# ESC.net
KiCad netlist of a schematic drawn in Altium Designer
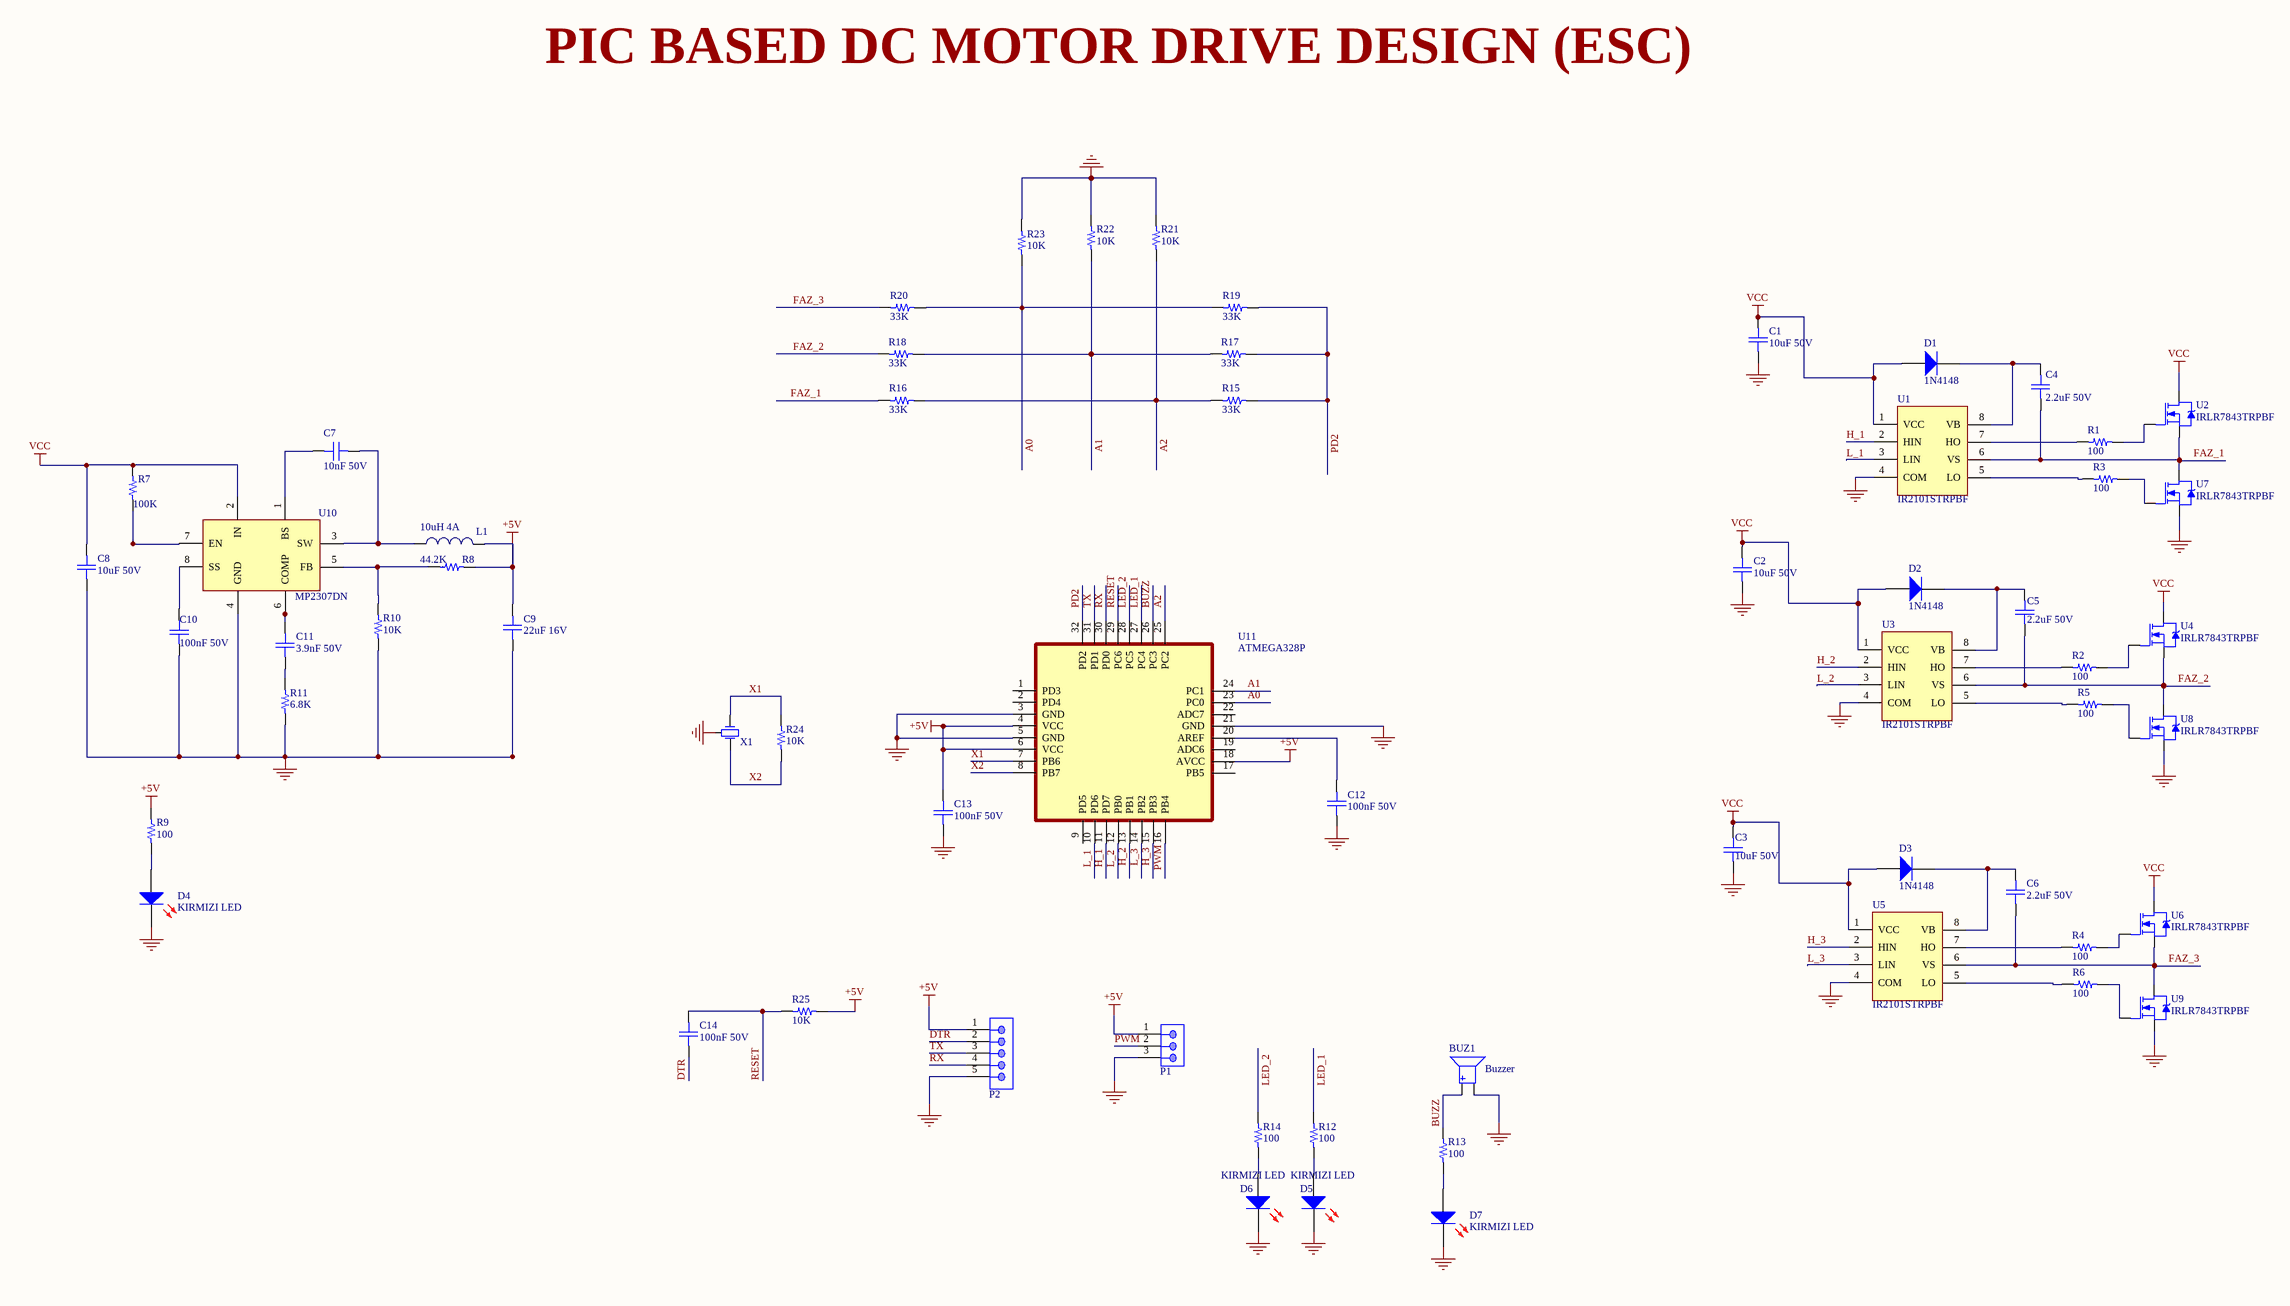
[diagram p0: ESC.SchDoc]

(export (version "E")
  (design (tool "Eeschema 10.0.6"))
  (components
    (comp (ref "BUZ1")
      (value "BUZZER MAGN 3.6V 7.5X7.5MM SMD")
      (footprint "BUZ: CMT-7525")
      (fields (field (name "DEGER") "Buzzer"))
      (libsource (lib "Suleyman Yukseldi") (part "Buzzer(CMT-7525-80-SMT-TR)"))
    )
    (comp (ref "C1")
      (value "CAP CER 10UF 50V X5R 1206")
      (footprint "CAP 1206/3216")
      (description "10µF ±10% 50V Ceramic Capacitor X5R 1206 (3216 Metric)")
      (fields (field (name "DEGER") "10uF 50V"))
      (libsource (lib "Suleyman Yukseldi") (part "10uF 50V 1206"))
    )
    (comp (ref "C2")
      (value "CAP CER 10UF 50V X5R 1206")
      (footprint "CAP 1206/3216")
      (description "10µF ±10% 50V Ceramic Capacitor X5R 1206 (3216 Metric)")
      (fields (field (name "DEGER") "10uF 50V"))
      (libsource (lib "Suleyman Yukseldi") (part "10uF 50V 1206"))
    )
    (comp (ref "C3")
      (value "CAP CER 10UF 50V X5R 1206")
      (footprint "CAP 1206/3216")
      (description "10µF ±10% 50V Ceramic Capacitor X5R 1206 (3216 Metric)")
      (fields (field (name "DEGER") "10uF 50V"))
      (libsource (lib "Suleyman Yukseldi") (part "10uF 50V 1206"))
    )
    (comp (ref "C4")
      (value "CAP CER 2.2UF 50V X5R 1206")
      (footprint "CAP 1206/3216")
      (description "2.2µF ±10% 50V Ceramic Capacitor X5R 1206 (3216 Metric)")
      (fields (field (name "DEGER") "2.2uF 50V"))
      (libsource (lib "Suleyman Yukseldi") (part "2.2uF 50V 1206"))
    )
    (comp (ref "C5")
      (value "CAP CER 2.2UF 50V X5R 1206")
      (footprint "CAP 1206/3216")
      (description "2.2µF ±10% 50V Ceramic Capacitor X5R 1206 (3216 Metric)")
      (fields (field (name "DEGER") "2.2uF 50V"))
      (libsource (lib "Suleyman Yukseldi") (part "2.2uF 50V 1206"))
    )
    (comp (ref "C6")
      (value "CAP CER 2.2UF 50V X5R 1206")
      (footprint "CAP 1206/3216")
      (description "2.2µF ±10% 50V Ceramic Capacitor X5R 1206 (3216 Metric)")
      (fields (field (name "DEGER") "2.2uF 50V"))
      (libsource (lib "Suleyman Yukseldi") (part "2.2uF 50V 1206"))
    )
    (comp (ref "C7")
      (value "CAP CER 10000PF 50V X7R 0805")
      (footprint "CAP 0805/2012")
      (description "10000pF ±10% 50V Ceramic Capacitor X7R 0805 (2012 Metric)")
      (fields (field (name "DEGER") "10nF 50V"))
      (libsource (lib "Suleyman Yukseldi") (part "10nF 50V 0805"))
    )
    (comp (ref "C8")
      (value "CAP CER 10UF 50V X5R 1206")
      (footprint "CAP 1206/3216")
      (description "10µF ±10% 50V Ceramic Capacitor X5R 1206 (3216 Metric)")
      (fields (field (name "DEGER") "10uF 50V"))
      (libsource (lib "Suleyman Yukseldi") (part "10uF 50V 1206"))
    )
    (comp (ref "C9")
      (value "CAP CERAMIC 22UF 16V X7S 20% PAD")
      (footprint "CAP 1206/3216")
      (description "22µF ±20% 16V Ceramic Capacitor X7S 1206 (3216 Metric)")
      (fields (field (name "DEGER") "22uF 16V"))
      (libsource (lib "Suleyman Yukseldi") (part "22uF 16V 1206"))
    )
    (comp (ref "C10")
      (value "CAP CER 0.1UF 50V X7R 0805")
      (footprint "CAP 0805/2012")
      (description "0.1µF ±10% 50V Ceramic Capacitor X7R 0805 (2012 Metric)")
      (fields (field (name "DEGER") "100nF 50V"))
      (libsource (lib "Suleyman Yukseldi") (part "100nF 50V 0805"))
    )
    (comp (ref "C11")
      (value "CAP CER 3900PF 50V X7R 0805")
      (footprint "CAP 0805/2012")
      (description "3900pF ±10% 50V Ceramic Capacitor X7R 0805 (2012 Metric)")
      (fields (field (name "DEGER") "3.9nF 50V"))
      (libsource (lib "Suleyman Yukseldi") (part "3.9nF 50V 0805"))
    )
    (comp (ref "C12")
      (value "CAP CER 0.1UF 50V X7R 0805")
      (footprint "CAP 0805/2012")
      (description "0.1µF ±10% 50V Ceramic Capacitor X7R 0805 (2012 Metric)")
      (fields (field (name "DEGER") "100nF 50V"))
      (libsource (lib "Suleyman Yukseldi") (part "100nF 50V 0805"))
    )
    (comp (ref "C13")
      (value "CAP CER 0.1UF 50V X7R 0805")
      (footprint "CAP 0805/2012")
      (description "0.1µF ±10% 50V Ceramic Capacitor X7R 0805 (2012 Metric)")
      (fields (field (name "DEGER") "100nF 50V"))
      (libsource (lib "Suleyman Yukseldi") (part "100nF 50V 0805"))
    )
    (comp (ref "C14")
      (value "CAP CER 0.1UF 50V X7R 0805")
      (footprint "CAP 0805/2012")
      (description "0.1µF ±10% 50V Ceramic Capacitor X7R 0805 (2012 Metric)")
      (fields (field (name "DEGER") "100nF 50V"))
      (libsource (lib "Suleyman Yukseldi") (part "100nF 50V 0805"))
    )
    (comp (ref "D1")
      (value "1N4148 Diyot")
      (footprint "SOD-123")
      (description "DIODE GEN PURP 100V 150MA SOD123")
      (fields (field (name "DEGER") "1N4148"))
      (libsource (lib "Suleyman Yukseldi") (part "1N4148"))
    )
    (comp (ref "D2")
      (value "1N4148 Diyot")
      (footprint "SOD-123")
      (description "DIODE GEN PURP 100V 150MA SOD123")
      (fields (field (name "DEGER") "1N4148"))
      (libsource (lib "Suleyman Yukseldi") (part "1N4148"))
    )
    (comp (ref "D3")
      (value "1N4148 Diyot")
      (footprint "SOD-123")
      (description "DIODE GEN PURP 100V 150MA SOD123")
      (fields (field (name "DEGER") "1N4148"))
      (libsource (lib "Suleyman Yukseldi") (part "1N4148"))
    )
    (comp (ref "D4")
      (value "Red 645nm LED Indication - Discrete 1.8V 0805")
      (footprint "SMD: LED 0805/2012 RED")
      (description "LED RED DIFFUSED 0805 SMD")
      (fields (field (name "DEGER") "KIRMIZI LED"))
      (libsource (lib "Suleyman Yukseldi") (part "LED_Kırmızı"))
    )
    (comp (ref "D5")
      (value "Red 645nm LED Indication - Discrete 1.8V 0805")
      (footprint "SMD: LED 0805/2012 RED")
      (description "LED RED DIFFUSED 0805 SMD")
      (fields (field (name "DEGER") "KIRMIZI LED"))
      (libsource (lib "Suleyman Yukseldi") (part "LED_Kırmızı"))
    )
    (comp (ref "D6")
      (value "Red 645nm LED Indication - Discrete 1.8V 0805")
      (footprint "SMD: LED 0805/2012 RED")
      (description "LED RED DIFFUSED 0805 SMD")
      (fields (field (name "DEGER") "KIRMIZI LED"))
      (libsource (lib "Suleyman Yukseldi") (part "LED_Kırmızı"))
    )
    (comp (ref "D7")
      (value "Red 645nm LED Indication - Discrete 1.8V 0805")
      (footprint "SMD: LED 0805/2012 RED")
      (description "LED RED DIFFUSED 0805 SMD")
      (fields (field (name "DEGER") "KIRMIZI LED"))
      (libsource (lib "Suleyman Yukseldi") (part "LED_Kırmızı"))
    )
    (comp (ref "L1")
      (value "FIXED IND 10UH 4A 68 MOHM SMD")
      (footprint "ASPI-0630LR-100M-T15")
      (description "10µH Shielded Molded Inductor 4A 68mOhm Max Nonstandard")
      (fields (field (name "DEGER") "10uH 4A"))
      (libsource (lib "Suleyman Yukseldi") (part "10uH 4A"))
    )
    (comp (ref "P1")
      (value "WR-PHD 2.54 mm Angled Socket Header")
      (footprint "PWM_CONN")
      (libsource (lib "Suleyman Yukseldi") (part "HDR(1X3)"))
    )
    (comp (ref "P2")
      (value "WR-PHD 2.54 mm Angled Socket Header")
      (footprint "TTL_CONN_5")
      (libsource (lib "Suleyman Yukseldi") (part "HDR(1X5)"))
    )
    (comp (ref "R1")
      (value "100")
      (footprint "RES_0805")
      (description "100 Ohms ±1% 0.125W, 1/8W Chip Resistor 0805 (2012 Metric) Moisture Resistant Thick Film")
      (libsource (lib "Suleyman Yukseldi") (part "100R 0805"))
    )
    (comp (ref "R2")
      (value "100")
      (footprint "RES_0805")
      (description "100 Ohms ±1% 0.125W, 1/8W Chip Resistor 0805 (2012 Metric) Moisture Resistant Thick Film")
      (libsource (lib "Suleyman Yukseldi") (part "100R 0805"))
    )
    (comp (ref "R3")
      (value "100")
      (footprint "RES_0805")
      (description "100 Ohms ±1% 0.125W, 1/8W Chip Resistor 0805 (2012 Metric) Moisture Resistant Thick Film")
      (libsource (lib "Suleyman Yukseldi") (part "100R 0805"))
    )
    (comp (ref "R4")
      (value "100")
      (footprint "RES_0805")
      (description "100 Ohms ±1% 0.125W, 1/8W Chip Resistor 0805 (2012 Metric) Moisture Resistant Thick Film")
      (libsource (lib "Suleyman Yukseldi") (part "100R 0805"))
    )
    (comp (ref "R5")
      (value "100")
      (footprint "RES_0805")
      (description "100 Ohms ±1% 0.125W, 1/8W Chip Resistor 0805 (2012 Metric) Moisture Resistant Thick Film")
      (libsource (lib "Suleyman Yukseldi") (part "100R 0805"))
    )
    (comp (ref "R6")
      (value "100")
      (footprint "RES_0805")
      (description "100 Ohms ±1% 0.125W, 1/8W Chip Resistor 0805 (2012 Metric) Moisture Resistant Thick Film")
      (libsource (lib "Suleyman Yukseldi") (part "100R 0805"))
    )
    (comp (ref "R7")
      (value "100K")
      (footprint "RES_0805")
      (description "100 kOhms ±1% 0.125W, 1/8W Chip Resistor 0805 (2012 Metric) Moisture Resistant Thick Film")
      (libsource (lib "Suleyman Yukseldi") (part "100K 0805"))
    )
    (comp (ref "R8")
      (value "44.2K")
      (footprint "RES_0805")
      (description "44.2 kOhms ±1% 0.125W, 1/8W Chip Resistor 0805 (2012 Metric) Moisture Resistant Thick Film")
      (libsource (lib "Suleyman Yukseldi") (part "44.2K 0805"))
    )
    (comp (ref "R9")
      (value "100")
      (footprint "RES_0805")
      (description "100 Ohms ±1% 0.125W, 1/8W Chip Resistor 0805 (2012 Metric) Moisture Resistant Thick Film")
      (libsource (lib "Suleyman Yukseldi") (part "100R 0805"))
    )
    (comp (ref "R10")
      (value "10K")
      (footprint "RES_0805")
      (description "10 kOhms ±1% 0.125W, 1/8W Chip Resistor 0805 (2012 Metric) Moisture Resistant Thick Film")
      (libsource (lib "Suleyman Yukseldi") (part "10K 0805"))
    )
    (comp (ref "R11")
      (value "6.8K")
      (footprint "RES_0805")
      (description "6.8 kOhms ±1% 0.125W, 1/8W Chip Resistor 0805 (2012 Metric) Moisture Resistant Thick Film")
      (libsource (lib "Suleyman Yukseldi") (part "6.8K 0805"))
    )
    (comp (ref "R12")
      (value "100")
      (footprint "RES_0805")
      (description "100 Ohms ±1% 0.125W, 1/8W Chip Resistor 0805 (2012 Metric) Moisture Resistant Thick Film")
      (libsource (lib "Suleyman Yukseldi") (part "100R 0805"))
    )
    (comp (ref "R13")
      (value "100")
      (footprint "RES_0805")
      (description "100 Ohms ±1% 0.125W, 1/8W Chip Resistor 0805 (2012 Metric) Moisture Resistant Thick Film")
      (libsource (lib "Suleyman Yukseldi") (part "100R 0805"))
    )
    (comp (ref "R14")
      (value "100")
      (footprint "RES_0805")
      (description "100 Ohms ±1% 0.125W, 1/8W Chip Resistor 0805 (2012 Metric) Moisture Resistant Thick Film")
      (libsource (lib "Suleyman Yukseldi") (part "100R 0805"))
    )
    (comp (ref "R15")
      (value "33K")
      (footprint "RES_0805")
      (description "33 kOhms ±1% 0.125W, 1/8W Chip Resistor 0805 (2012 Metric) Moisture Resistant Thick Film")
      (libsource (lib "Suleyman Yukseldi") (part "33K 0805"))
    )
    (comp (ref "R16")
      (value "33K")
      (footprint "RES_0805")
      (description "33 kOhms ±1% 0.125W, 1/8W Chip Resistor 0805 (2012 Metric) Moisture Resistant Thick Film")
      (libsource (lib "Suleyman Yukseldi") (part "33K 0805"))
    )
    (comp (ref "R17")
      (value "33K")
      (footprint "RES_0805")
      (description "33 kOhms ±1% 0.125W, 1/8W Chip Resistor 0805 (2012 Metric) Moisture Resistant Thick Film")
      (libsource (lib "Suleyman Yukseldi") (part "33K 0805"))
    )
    (comp (ref "R18")
      (value "33K")
      (footprint "RES_0805")
      (description "33 kOhms ±1% 0.125W, 1/8W Chip Resistor 0805 (2012 Metric) Moisture Resistant Thick Film")
      (libsource (lib "Suleyman Yukseldi") (part "33K 0805"))
    )
    (comp (ref "R19")
      (value "33K")
      (footprint "RES_0805")
      (description "33 kOhms ±1% 0.125W, 1/8W Chip Resistor 0805 (2012 Metric) Moisture Resistant Thick Film")
      (libsource (lib "Suleyman Yukseldi") (part "33K 0805"))
    )
    (comp (ref "R20")
      (value "33K")
      (footprint "RES_0805")
      (description "33 kOhms ±1% 0.125W, 1/8W Chip Resistor 0805 (2012 Metric) Moisture Resistant Thick Film")
      (libsource (lib "Suleyman Yukseldi") (part "33K 0805"))
    )
    (comp (ref "R21")
      (value "10K")
      (footprint "RES_0805")
      (description "10 kOhms ±1% 0.125W, 1/8W Chip Resistor 0805 (2012 Metric) Moisture Resistant Thick Film")
      (libsource (lib "Suleyman Yukseldi") (part "10K 0805"))
    )
    (comp (ref "R22")
      (value "10K")
      (footprint "RES_0805")
      (description "10 kOhms ±1% 0.125W, 1/8W Chip Resistor 0805 (2012 Metric) Moisture Resistant Thick Film")
      (libsource (lib "Suleyman Yukseldi") (part "10K 0805"))
    )
    (comp (ref "R23")
      (value "10K")
      (footprint "RES_0805")
      (description "10 kOhms ±1% 0.125W, 1/8W Chip Resistor 0805 (2012 Metric) Moisture Resistant Thick Film")
      (libsource (lib "Suleyman Yukseldi") (part "10K 0805"))
    )
    (comp (ref "R24")
      (value "10K")
      (footprint "RES_0805")
      (description "10 kOhms ±1% 0.125W, 1/8W Chip Resistor 0805 (2012 Metric) Moisture Resistant Thick Film")
      (libsource (lib "Suleyman Yukseldi") (part "10K 0805"))
    )
    (comp (ref "R25")
      (value "10K")
      (footprint "RES_0805")
      (description "10 kOhms ±1% 0.125W, 1/8W Chip Resistor 0805 (2012 Metric) Moisture Resistant Thick Film")
      (libsource (lib "Suleyman Yukseldi") (part "10K 0805"))
    )
    (comp (ref "U1")
      (value "IC GATE DRVR HALF-BRIDGE 8SOIC")
      (footprint "SOIC8")
      (description "Half-Bridge Gate Driver IC Non-Inverting 8-SOIC")
      (fields (field (name "DEGER") "IR2101STRPBF"))
      (libsource (lib "Suleyman Yukseldi") (part "IR2101"))
    )
    (comp (ref "U2")
      (value "MOSFET N-CH 30V 161A DPAK")
      (footprint "DPAK")
      (description "N-Channel 30V 161A (Tc) 140W (Tc) Surface Mount D-Pak")
      (fields (field (name "DEGER") "IRLR7843TRPBF"))
      (libsource (lib "Suleyman Yukseldi") (part "IRLR7843"))
    )
    (comp (ref "U3")
      (value "IC GATE DRVR HALF-BRIDGE 8SOIC")
      (footprint "SOIC8")
      (description "Half-Bridge Gate Driver IC Non-Inverting 8-SOIC")
      (fields (field (name "DEGER") "IR2101STRPBF"))
      (libsource (lib "Suleyman Yukseldi") (part "IR2101"))
    )
    (comp (ref "U4")
      (value "MOSFET N-CH 30V 161A DPAK")
      (footprint "DPAK")
      (description "N-Channel 30V 161A (Tc) 140W (Tc) Surface Mount D-Pak")
      (fields (field (name "DEGER") "IRLR7843TRPBF"))
      (libsource (lib "Suleyman Yukseldi") (part "IRLR7843"))
    )
    (comp (ref "U5")
      (value "IC GATE DRVR HALF-BRIDGE 8SOIC")
      (footprint "SOIC8")
      (description "Half-Bridge Gate Driver IC Non-Inverting 8-SOIC")
      (fields (field (name "DEGER") "IR2101STRPBF"))
      (libsource (lib "Suleyman Yukseldi") (part "IR2101"))
    )
    (comp (ref "U6")
      (value "MOSFET N-CH 30V 161A DPAK")
      (footprint "DPAK")
      (description "N-Channel 30V 161A (Tc) 140W (Tc) Surface Mount D-Pak")
      (fields (field (name "DEGER") "IRLR7843TRPBF"))
      (libsource (lib "Suleyman Yukseldi") (part "IRLR7843"))
    )
    (comp (ref "U7")
      (value "MOSFET N-CH 30V 161A DPAK")
      (footprint "DPAK")
      (description "N-Channel 30V 161A (Tc) 140W (Tc) Surface Mount D-Pak")
      (fields (field (name "DEGER") "IRLR7843TRPBF"))
      (libsource (lib "Suleyman Yukseldi") (part "IRLR7843"))
    )
    (comp (ref "U8")
      (value "MOSFET N-CH 30V 161A DPAK")
      (footprint "DPAK")
      (description "N-Channel 30V 161A (Tc) 140W (Tc) Surface Mount D-Pak")
      (fields (field (name "DEGER") "IRLR7843TRPBF"))
      (libsource (lib "Suleyman Yukseldi") (part "IRLR7843"))
    )
    (comp (ref "U9")
      (value "MOSFET N-CH 30V 161A DPAK")
      (footprint "DPAK")
      (description "N-Channel 30V 161A (Tc) 140W (Tc) Surface Mount D-Pak")
      (fields (field (name "DEGER") "IRLR7843TRPBF"))
      (libsource (lib "Suleyman Yukseldi") (part "IRLR7843"))
    )
    (comp (ref "U10")
      (value "IC REG BUCK ADJUSTABLE 3A 8SOIC")
      (footprint "SOIC8_PAD")
      (fields (field (name "DEGER") "MP2307DN"))
      (libsource (lib "Suleyman Yukseldi") (part "MP2307DN"))
    )
    (comp (ref "U11")
      (value "IC MCU 8BIT 32KB FLASH 32TQFP")
      (footprint "TQFP32")
      (description "AVR AVR® ATmega Microcontroller IC 8-Bit 20MHz 32KB (16K x 16) FLASH 32-TQFP (7x7)")
      (fields (field (name "DEGER") "ATMEGA328P"))
      (libsource (lib "Suleyman Yukseldi") (part "ATMEGA328P"))
    )
    (comp (ref "X1")
      (value "CERAMIC RES 16.0000MHZ 15PF SMD")
      (footprint "CRYSTAL_16MHZ(CTSE16)")
      (description "16MHz Ceramic Resonator Built in Capacitor 15pF ±0.3%  -20°C ~ 80°C Surface Mount")
      (libsource (lib "Suleyman Yukseldi") (part "CRYSTAL 16.0000MHZ(CSTCE16M0V53-R0)"))
    )
  )
  (nets
    (net (code "1") (name "+5V") (class "Default")
      (node (ref "C13") (pin "2") (pinfunction "2_2") (pintype "passive"))
      (node (ref "C9") (pin "2") (pinfunction "2_2") (pintype "passive"))
      (node (ref "L1") (pin "2") (pinfunction "2_2") (pintype "passive"))
      (node (ref "P1") (pin "1") (pinfunction "1_1") (pintype "passive"))
      (node (ref "P2") (pin "1") (pinfunction "1_1") (pintype "passive"))
      (node (ref "R25") (pin "2") (pinfunction "2_2") (pintype "passive"))
      (node (ref "R8") (pin "2") (pinfunction "2_2") (pintype "passive"))
      (node (ref "R9") (pin "2") (pinfunction "2_2") (pintype "passive"))
      (node (ref "U11") (pin "18") (pinfunction "AVCC_18") (pintype "passive"))
      (node (ref "U11") (pin "4") (pinfunction "VCC_4") (pintype "passive"))
      (node (ref "U11") (pin "6") (pinfunction "VCC_6") (pintype "passive"))
    )
    (net (code "2") (name "/A0") (class "Default")
      (node (ref "R19") (pin "2") (pinfunction "2_2") (pintype "passive"))
      (node (ref "R20") (pin "1") (pinfunction "1_1") (pintype "passive"))
      (node (ref "R23") (pin "2") (pinfunction "2_2") (pintype "passive"))
      (node (ref "U11") (pin "23") (pinfunction "PC0_23") (pintype "passive"))
    )
    (net (code "3") (name "/A1") (class "Default")
      (node (ref "R17") (pin "2") (pinfunction "2_2") (pintype "passive"))
      (node (ref "R18") (pin "1") (pinfunction "1_1") (pintype "passive"))
      (node (ref "R22") (pin "2") (pinfunction "2_2") (pintype "passive"))
      (node (ref "U11") (pin "24") (pinfunction "PC1_24") (pintype "passive"))
    )
    (net (code "4") (name "/A2") (class "Default")
      (node (ref "R15") (pin "2") (pinfunction "2_2") (pintype "passive"))
      (node (ref "R16") (pin "1") (pinfunction "1_1") (pintype "passive"))
      (node (ref "R21") (pin "2") (pinfunction "2_2") (pintype "passive"))
      (node (ref "U11") (pin "25") (pinfunction "PC2_25") (pintype "passive"))
    )
    (net (code "5") (name "/BUZZ") (class "Default")
      (node (ref "BUZ1") (pin "1") (pinfunction "Positive_1") (pintype "passive"))
      (node (ref "R13") (pin "2") (pinfunction "2_2") (pintype "passive"))
      (node (ref "U11") (pin "26") (pinfunction "PC3_26") (pintype "passive"))
    )
    (net (code "6") (name "/DTR") (class "Default")
      (node (ref "C14") (pin "1") (pinfunction "1_1") (pintype "passive"))
      (node (ref "P2") (pin "2") (pinfunction "2_2") (pintype "passive"))
    )
    (net (code "7") (name "/FAZ_1") (class "Default")
      (node (ref "C4") (pin "1") (pinfunction "1_1") (pintype "passive"))
      (node (ref "R16") (pin "2") (pinfunction "2_2") (pintype "passive"))
      (node (ref "U1") (pin "6") (pinfunction "VS_6") (pintype "passive"))
      (node (ref "U2") (pin "3") (pinfunction "S_3") (pintype "passive"))
      (node (ref "U7") (pin "4") (pinfunction "D_4") (pintype "passive"))
    )
    (net (code "8") (name "/FAZ_2") (class "Default")
      (node (ref "C5") (pin "1") (pinfunction "1_1") (pintype "passive"))
      (node (ref "R18") (pin "2") (pinfunction "2_2") (pintype "passive"))
      (node (ref "U3") (pin "6") (pinfunction "VS_6") (pintype "passive"))
      (node (ref "U4") (pin "3") (pinfunction "S_3") (pintype "passive"))
      (node (ref "U8") (pin "4") (pinfunction "D_4") (pintype "passive"))
    )
    (net (code "9") (name "/FAZ_3") (class "Default")
      (node (ref "C6") (pin "1") (pinfunction "1_1") (pintype "passive"))
      (node (ref "R20") (pin "2") (pinfunction "2_2") (pintype "passive"))
      (node (ref "U5") (pin "6") (pinfunction "VS_6") (pintype "passive"))
      (node (ref "U6") (pin "3") (pinfunction "S_3") (pintype "passive"))
      (node (ref "U9") (pin "4") (pinfunction "D_4") (pintype "passive"))
    )
    (net (code "10") (name "/H_1") (class "Default")
      (node (ref "U1") (pin "2") (pinfunction "HIN_2") (pintype "passive"))
      (node (ref "U11") (pin "11") (pinfunction "PD7_11") (pintype "passive"))
    )
    (net (code "11") (name "/H_2") (class "Default")
      (node (ref "U11") (pin "13") (pinfunction "PB1_13") (pintype "passive"))
      (node (ref "U3") (pin "2") (pinfunction "HIN_2") (pintype "passive"))
    )
    (net (code "12") (name "/H_3") (class "Default")
      (node (ref "U11") (pin "15") (pinfunction "PB3_15") (pintype "passive"))
      (node (ref "U5") (pin "2") (pinfunction "HIN_2") (pintype "passive"))
    )
    (net (code "13") (name "/LED_1") (class "Default")
      (node (ref "R12") (pin "2") (pinfunction "2_2") (pintype "passive"))
      (node (ref "U11") (pin "27") (pinfunction "PC4_27") (pintype "passive"))
    )
    (net (code "14") (name "/LED_2") (class "Default")
      (node (ref "R14") (pin "2") (pinfunction "2_2") (pintype "passive"))
      (node (ref "U11") (pin "28") (pinfunction "PC5_28") (pintype "passive"))
    )
    (net (code "15") (name "/L_1") (class "Default")
      (node (ref "U1") (pin "3") (pinfunction "LIN_3") (pintype "passive"))
      (node (ref "U11") (pin "10") (pinfunction "PD6_10") (pintype "passive"))
    )
    (net (code "16") (name "/L_2") (class "Default")
      (node (ref "U11") (pin "12") (pinfunction "PB0_12") (pintype "passive"))
      (node (ref "U3") (pin "3") (pinfunction "LIN_3") (pintype "passive"))
    )
    (net (code "17") (name "/L_3") (class "Default")
      (node (ref "U11") (pin "14") (pinfunction "PB2_14") (pintype "passive"))
      (node (ref "U5") (pin "3") (pinfunction "LIN_3") (pintype "passive"))
    )
    (net (code "18") (name "/PD2") (class "Default")
      (node (ref "R15") (pin "1") (pinfunction "1_1") (pintype "passive"))
      (node (ref "R17") (pin "1") (pinfunction "1_1") (pintype "passive"))
      (node (ref "R19") (pin "1") (pinfunction "1_1") (pintype "passive"))
      (node (ref "U11") (pin "32") (pinfunction "PD2_32") (pintype "passive"))
    )
    (net (code "19") (name "/PWM") (class "Default")
      (node (ref "P1") (pin "2") (pinfunction "2_2") (pintype "passive"))
      (node (ref "U11") (pin "16") (pinfunction "PB4_16") (pintype "passive"))
    )
    (net (code "20") (name "/RESET") (class "Default")
      (node (ref "C14") (pin "2") (pinfunction "2_2") (pintype "passive"))
      (node (ref "R25") (pin "1") (pinfunction "1_1") (pintype "passive"))
      (node (ref "U11") (pin "29") (pinfunction "PC6_29") (pintype "passive"))
    )
    (net (code "21") (name "/RX") (class "Default")
      (node (ref "P2") (pin "4") (pinfunction "4_4") (pintype "passive"))
      (node (ref "U11") (pin "30") (pinfunction "PD0_30") (pintype "passive"))
    )
    (net (code "22") (name "/TX") (class "Default")
      (node (ref "P2") (pin "3") (pinfunction "3_3") (pintype "passive"))
      (node (ref "U11") (pin "31") (pinfunction "PD1_31") (pintype "passive"))
    )
    (net (code "23") (name "/X1") (class "Default")
      (node (ref "R24") (pin "1") (pinfunction "1_1") (pintype "passive"))
      (node (ref "U11") (pin "7") (pinfunction "PB6_7") (pintype "passive"))
      (node (ref "X1") (pin "1") (pinfunction "OSC1_1") (pintype "passive"))
    )
    (net (code "24") (name "/X2") (class "Default")
      (node (ref "R24") (pin "2") (pinfunction "2_2") (pintype "passive"))
      (node (ref "U11") (pin "8") (pinfunction "PB7_8") (pintype "passive"))
      (node (ref "X1") (pin "3") (pinfunction "OSC2_3") (pintype "passive"))
    )
    (net (code "25") (name "GND") (class "Default")
      (node (ref "BUZ1") (pin "2") (pinfunction "Negative_2") (pintype "passive"))
      (node (ref "C1") (pin "1") (pinfunction "1_1") (pintype "passive"))
      (node (ref "C10") (pin "1") (pinfunction "1_1") (pintype "passive"))
      (node (ref "C12") (pin "1") (pinfunction "1_1") (pintype "passive"))
      (node (ref "C13") (pin "1") (pinfunction "1_1") (pintype "passive"))
      (node (ref "C2") (pin "1") (pinfunction "1_1") (pintype "passive"))
      (node (ref "C3") (pin "1") (pinfunction "1_1") (pintype "passive"))
      (node (ref "C8") (pin "1") (pinfunction "1_1") (pintype "passive"))
      (node (ref "C9") (pin "1") (pinfunction "1_1") (pintype "passive"))
      (node (ref "D4") (pin "2") (pinfunction "K_2") (pintype "passive"))
      (node (ref "D5") (pin "2") (pinfunction "K_2") (pintype "passive"))
      (node (ref "D6") (pin "2") (pinfunction "K_2") (pintype "passive"))
      (node (ref "D7") (pin "2") (pinfunction "K_2") (pintype "passive"))
      (node (ref "P1") (pin "3") (pinfunction "3_3") (pintype "passive"))
      (node (ref "P2") (pin "5") (pinfunction "5_5") (pintype "passive"))
      (node (ref "R10") (pin "1") (pinfunction "1_1") (pintype "passive"))
      (node (ref "R11") (pin "1") (pinfunction "1_1") (pintype "passive"))
      (node (ref "R21") (pin "1") (pinfunction "1_1") (pintype "passive"))
      (node (ref "R22") (pin "1") (pinfunction "1_1") (pintype "passive"))
      (node (ref "R23") (pin "1") (pinfunction "1_1") (pintype "passive"))
      (node (ref "U1") (pin "4") (pinfunction "COM_4") (pintype "passive"))
      (node (ref "U10") (pin "4") (pinfunction "GND_4") (pintype "passive"))
      (node (ref "U11") (pin "21") (pinfunction "GND_21") (pintype "passive"))
      (node (ref "U11") (pin "3") (pinfunction "GND_3") (pintype "passive"))
      (node (ref "U11") (pin "5") (pinfunction "GND_5") (pintype "passive"))
      (node (ref "U3") (pin "4") (pinfunction "COM_4") (pintype "passive"))
      (node (ref "U5") (pin "4") (pinfunction "COM_4") (pintype "passive"))
      (node (ref "U7") (pin "3") (pinfunction "S_3") (pintype "passive"))
      (node (ref "U8") (pin "3") (pinfunction "S_3") (pintype "passive"))
      (node (ref "U9") (pin "3") (pinfunction "S_3") (pintype "passive"))
      (node (ref "X1") (pin "2") (pinfunction "GND_2") (pintype "passive"))
    )
    (net (code "26") (name "Net-(C11-Pad1)") (class "Default")
      (node (ref "C11") (pin "1") (pinfunction "1_1") (pintype "passive"))
      (node (ref "R11") (pin "2") (pinfunction "2_2") (pintype "passive"))
    )
    (net (code "27") (name "Net-(D1-K)") (class "Default")
      (node (ref "C4") (pin "2") (pinfunction "2_2") (pintype "passive"))
      (node (ref "D1") (pin "2") (pinfunction "K_2") (pintype "passive"))
      (node (ref "U1") (pin "8") (pinfunction "VB_8") (pintype "passive"))
    )
    (net (code "28") (name "Net-(D2-K)") (class "Default")
      (node (ref "C5") (pin "2") (pinfunction "2_2") (pintype "passive"))
      (node (ref "D2") (pin "2") (pinfunction "K_2") (pintype "passive"))
      (node (ref "U3") (pin "8") (pinfunction "VB_8") (pintype "passive"))
    )
    (net (code "29") (name "Net-(D3-K)") (class "Default")
      (node (ref "C6") (pin "2") (pinfunction "2_2") (pintype "passive"))
      (node (ref "D3") (pin "2") (pinfunction "K_2") (pintype "passive"))
      (node (ref "U5") (pin "8") (pinfunction "VB_8") (pintype "passive"))
    )
    (net (code "30") (name "Net-(D4-A)") (class "Default")
      (node (ref "D4") (pin "1") (pinfunction "A_1") (pintype "passive"))
      (node (ref "R9") (pin "1") (pinfunction "1_1") (pintype "passive"))
    )
    (net (code "31") (name "Net-(D5-A)") (class "Default")
      (node (ref "D5") (pin "1") (pinfunction "A_1") (pintype "passive"))
      (node (ref "R12") (pin "1") (pinfunction "1_1") (pintype "passive"))
    )
    (net (code "32") (name "Net-(D6-A)") (class "Default")
      (node (ref "D6") (pin "1") (pinfunction "A_1") (pintype "passive"))
      (node (ref "R14") (pin "1") (pinfunction "1_1") (pintype "passive"))
    )
    (net (code "33") (name "Net-(D7-A)") (class "Default")
      (node (ref "D7") (pin "1") (pinfunction "A_1") (pintype "passive"))
      (node (ref "R13") (pin "1") (pinfunction "1_1") (pintype "passive"))
    )
    (net (code "34") (name "Net-(U1-HO)") (class "Default")
      (node (ref "R1") (pin "1") (pinfunction "1_1") (pintype "passive"))
      (node (ref "U1") (pin "7") (pinfunction "HO_7") (pintype "passive"))
    )
    (net (code "35") (name "Net-(U1-LO)") (class "Default")
      (node (ref "R3") (pin "1") (pinfunction "1_1") (pintype "passive"))
      (node (ref "U1") (pin "5") (pinfunction "LO_5") (pintype "passive"))
    )
    (net (code "36") (name "Net-(U2-G)") (class "Default")
      (node (ref "R1") (pin "2") (pinfunction "2_2") (pintype "passive"))
      (node (ref "U2") (pin "1") (pinfunction "G_1") (pintype "passive"))
    )
    (net (code "37") (name "Net-(U3-HO)") (class "Default")
      (node (ref "R2") (pin "1") (pinfunction "1_1") (pintype "passive"))
      (node (ref "U3") (pin "7") (pinfunction "HO_7") (pintype "passive"))
    )
    (net (code "38") (name "Net-(U3-LO)") (class "Default")
      (node (ref "R5") (pin "1") (pinfunction "1_1") (pintype "passive"))
      (node (ref "U3") (pin "5") (pinfunction "LO_5") (pintype "passive"))
    )
    (net (code "39") (name "Net-(U4-G)") (class "Default")
      (node (ref "R2") (pin "2") (pinfunction "2_2") (pintype "passive"))
      (node (ref "U4") (pin "1") (pinfunction "G_1") (pintype "passive"))
    )
    (net (code "40") (name "Net-(U5-HO)") (class "Default")
      (node (ref "R4") (pin "1") (pinfunction "1_1") (pintype "passive"))
      (node (ref "U5") (pin "7") (pinfunction "HO_7") (pintype "passive"))
    )
    (net (code "41") (name "Net-(U5-LO)") (class "Default")
      (node (ref "R6") (pin "1") (pinfunction "1_1") (pintype "passive"))
      (node (ref "U5") (pin "5") (pinfunction "LO_5") (pintype "passive"))
    )
    (net (code "42") (name "Net-(U6-G)") (class "Default")
      (node (ref "R4") (pin "2") (pinfunction "2_2") (pintype "passive"))
      (node (ref "U6") (pin "1") (pinfunction "G_1") (pintype "passive"))
    )
    (net (code "43") (name "Net-(U7-G)") (class "Default")
      (node (ref "R3") (pin "2") (pinfunction "2_2") (pintype "passive"))
      (node (ref "U7") (pin "1") (pinfunction "G_1") (pintype "passive"))
    )
    (net (code "44") (name "Net-(U8-G)") (class "Default")
      (node (ref "R5") (pin "2") (pinfunction "2_2") (pintype "passive"))
      (node (ref "U8") (pin "1") (pinfunction "G_1") (pintype "passive"))
    )
    (net (code "45") (name "Net-(U9-G)") (class "Default")
      (node (ref "R6") (pin "2") (pinfunction "2_2") (pintype "passive"))
      (node (ref "U9") (pin "1") (pinfunction "G_1") (pintype "passive"))
    )
    (net (code "46") (name "Net-(U10-BS)") (class "Default")
      (node (ref "C7") (pin "1") (pinfunction "1_1") (pintype "passive"))
      (node (ref "U10") (pin "1") (pinfunction "BS_1") (pintype "passive"))
    )
    (net (code "47") (name "Net-(U10-COMP)") (class "Default")
      (node (ref "C11") (pin "2") (pinfunction "2_2") (pintype "passive"))
      (node (ref "U10") (pin "6") (pinfunction "COMP_6") (pintype "passive"))
    )
    (net (code "48") (name "Net-(U10-EN)") (class "Default")
      (node (ref "R7") (pin "1") (pinfunction "1_1") (pintype "passive"))
      (node (ref "U10") (pin "7") (pinfunction "EN_7") (pintype "passive"))
    )
    (net (code "49") (name "Net-(U10-FB)") (class "Default")
      (node (ref "R10") (pin "2") (pinfunction "2_2") (pintype "passive"))
      (node (ref "R8") (pin "1") (pinfunction "1_1") (pintype "passive"))
      (node (ref "U10") (pin "5") (pinfunction "FB_5") (pintype "passive"))
    )
    (net (code "50") (name "Net-(U10-SS)") (class "Default")
      (node (ref "C10") (pin "2") (pinfunction "2_2") (pintype "passive"))
      (node (ref "U10") (pin "8") (pinfunction "SS_8") (pintype "passive"))
    )
    (net (code "51") (name "Net-(U10-SW)") (class "Default")
      (node (ref "C7") (pin "2") (pinfunction "2_2") (pintype "passive"))
      (node (ref "L1") (pin "1") (pinfunction "1_1") (pintype "passive"))
      (node (ref "U10") (pin "3") (pinfunction "SW_3") (pintype "passive"))
    )
    (net (code "52") (name "Net-(U11-AREF)") (class "Default")
      (node (ref "C12") (pin "2") (pinfunction "2_2") (pintype "passive"))
      (node (ref "U11") (pin "20") (pinfunction "AREF_20") (pintype "passive"))
    )
    (net (code "53") (name "VCC") (class "Default")
      (node (ref "C1") (pin "2") (pinfunction "2_2") (pintype "passive"))
      (node (ref "C2") (pin "2") (pinfunction "2_2") (pintype "passive"))
      (node (ref "C3") (pin "2") (pinfunction "2_2") (pintype "passive"))
      (node (ref "C8") (pin "2") (pinfunction "2_2") (pintype "passive"))
      (node (ref "D1") (pin "1") (pinfunction "A_1") (pintype "passive"))
      (node (ref "D2") (pin "1") (pinfunction "A_1") (pintype "passive"))
      (node (ref "D3") (pin "1") (pinfunction "A_1") (pintype "passive"))
      (node (ref "R7") (pin "2") (pinfunction "2_2") (pintype "passive"))
      (node (ref "U1") (pin "1") (pinfunction "VCC_1") (pintype "passive"))
      (node (ref "U10") (pin "2") (pinfunction "IN_2") (pintype "passive"))
      (node (ref "U2") (pin "4") (pinfunction "D_4") (pintype "passive"))
      (node (ref "U3") (pin "1") (pinfunction "VCC_1") (pintype "passive"))
      (node (ref "U4") (pin "4") (pinfunction "D_4") (pintype "passive"))
      (node (ref "U5") (pin "1") (pinfunction "VCC_1") (pintype "passive"))
      (node (ref "U6") (pin "4") (pinfunction "D_4") (pintype "passive"))
    )
    (net (code "54") (name "unconnected-(U11-ADC6-Pad19)") (class "Default")
      (node (ref "U11") (pin "19") (pinfunction "ADC6_19") (pintype "passive"))
    )
    (net (code "55") (name "unconnected-(U11-ADC7-Pad22)") (class "Default")
      (node (ref "U11") (pin "22") (pinfunction "ADC7_22") (pintype "passive"))
    )
    (net (code "56") (name "unconnected-(U11-PB5-Pad17)") (class "Default")
      (node (ref "U11") (pin "17") (pinfunction "PB5_17") (pintype "passive"))
    )
    (net (code "57") (name "unconnected-(U11-PD3-Pad1)") (class "Default")
      (node (ref "U11") (pin "1") (pinfunction "PD3_1") (pintype "passive"))
    )
    (net (code "58") (name "unconnected-(U11-PD4-Pad2)") (class "Default")
      (node (ref "U11") (pin "2") (pinfunction "PD4_2") (pintype "passive"))
    )
    (net (code "59") (name "unconnected-(U11-PD5-Pad9)") (class "Default")
      (node (ref "U11") (pin "9") (pinfunction "PD5_9") (pintype "passive"))
    )
  )
)
